# SCH_PCB_LAMOS_Moteur_2025-04-08.net
KiCad netlist of a schematic drawn in EasyEDA
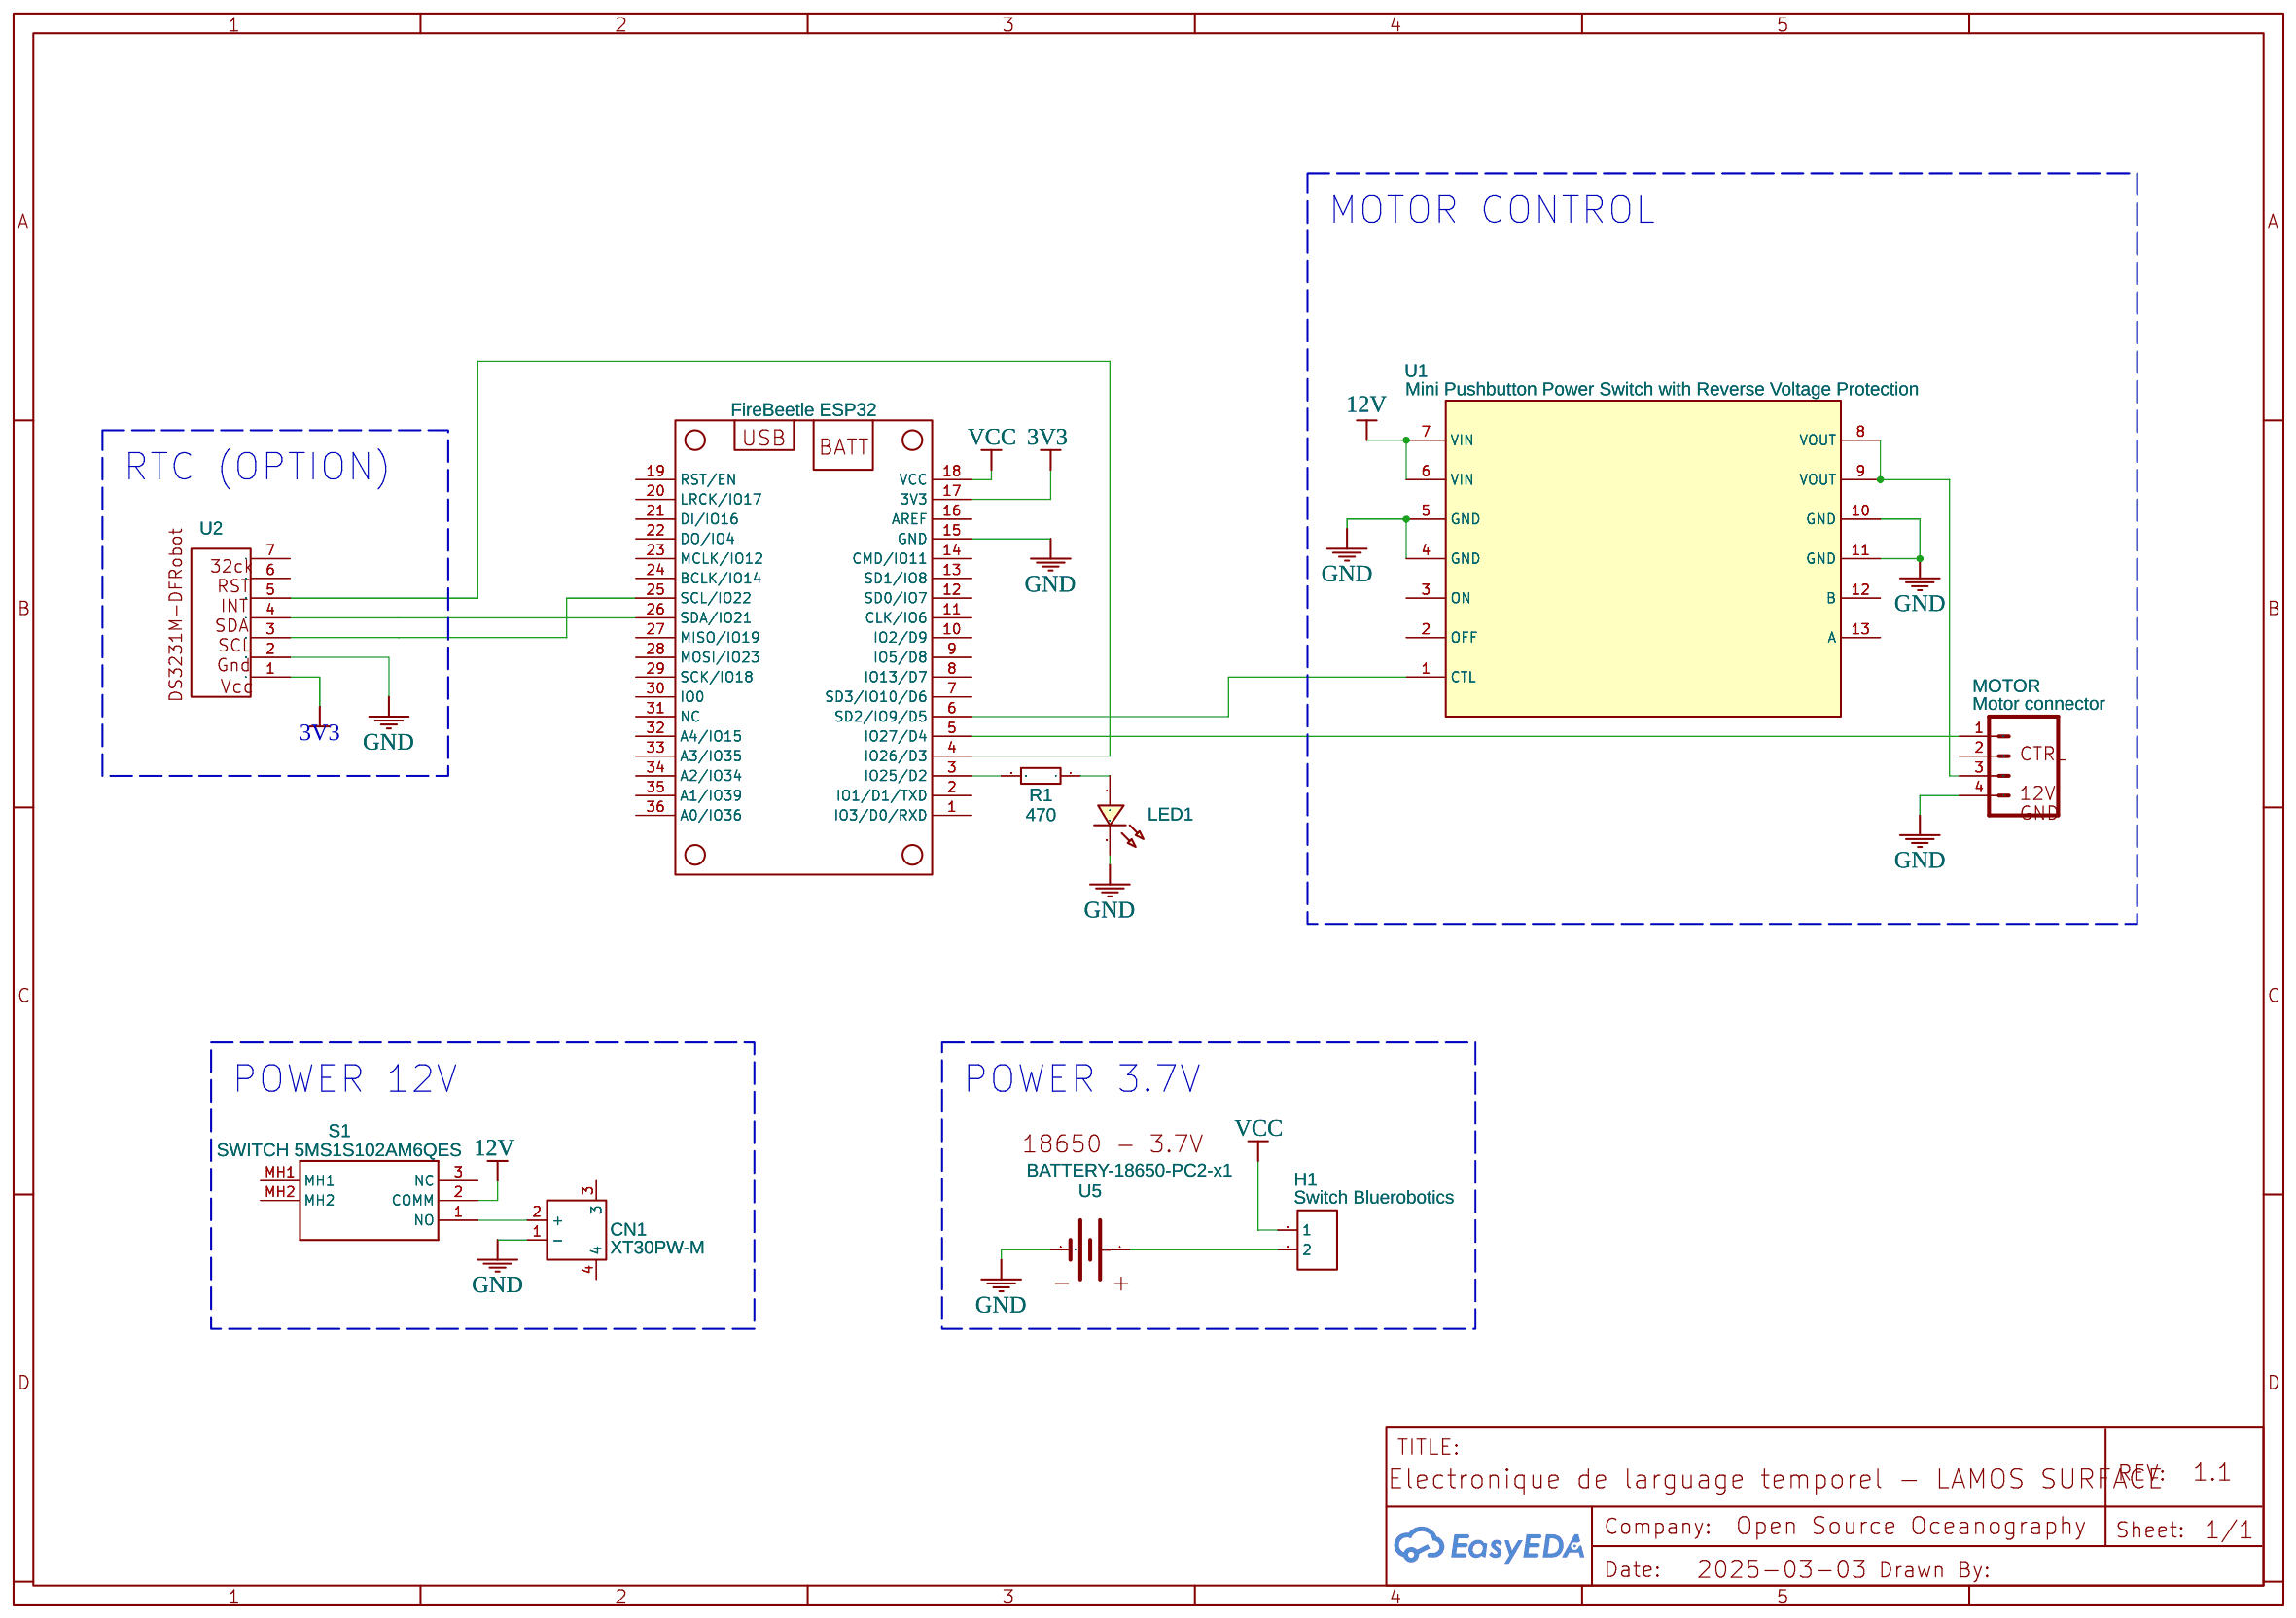
[diagram p0: schematic sheet]

(export (version "E")
  (design (tool "Eeschema 10.0.6"))
  (components
    (comp (ref "CN1")
      (value "XT30PW-M")
      (fields (field (name "Manufacturer Part") "XT30PW-M30.G.Y") (field (name "Manufacturer") "AMASS(艾迈斯)"))
      (libsource (lib "") (part "XT30PW-M"))
    )
    (comp (ref "ESP32-FB")
      (value "FireBeetle ESP32")
      (fields (field (name "Manufacturer Part") "?"))
      (libsource (lib "") (part "Unknown_405_-510"))
    )
    (comp (ref "H1") (value "Switch Bluerobotics") (libsource (lib "") (part "HDR-F-2.54_1x2")))
    (comp (ref "LED1")
      (value "LED-TH-3mm_G")
      (fields
        (field (name "Manufacturer Part") "204-10SYGD/S530-E3")
        (field (name "Manufacturer") "EVERLIGHT(台湾亿光)")
      )
      (libsource (lib "") (part "LED-TH-3mm_G"))
    )
    (comp (ref "MOTOR")
      (value "Motor connector")
      (fields (field (name "Manufacturer Part") "?"))
      (libsource (lib "") (part "Unknown_1010_-425"))
    )
    (comp (ref "R1")
      (value "470")
      (fields (field (name "Manufacturer Part") "?"))
      (libsource (lib "") (part "Res_AXIAL-0.3(1/8W)_EU"))
    )
    (comp (ref "S1") (value "SWITCH 5MS1S102AM6QES") (libsource (lib "") (part "5MS1S102AM6QES")))
    (comp (ref "U1")
      (value "Mini Pushbutton Power Switch with Reverse Voltage Protection")
      (libsource (lib "") (part "Mini Pushbutton Power Switch with Reverse Voltage Protection"))
    )
    (comp (ref "U2")
      (value "DS3231_DFRobot")
      (fields (field (name "Manufacturer Part") "DS3231M MEMS") (field (name "Manufacturer") "DFROBOT"))
      (libsource (lib "") (part "DS3231_DFRobot"))
    )
    (comp (ref "U5") (value "BATTERY-18650-PC2-x1") (libsource (lib "") (part "BATTERY-18650-PC2-x1")))
  )
  (nets
    (net (code "1") (name "3V3") (class "Default")
      (node (ref "ESP32-FB") (pin "17") (pinfunction "3V3_17") (pintype "unspecified"))
      (node (ref "U2") (pin "1") (pinfunction "1_1") (pintype "unspecified"))
    )
    (net (code "2") (name "12V") (class "Default")
      (node (ref "S1") (pin "2") (pinfunction "COMM_2") (pintype "bidirectional"))
      (node (ref "U1") (pin "6") (pinfunction "VIN_6") (pintype "unspecified"))
      (node (ref "U1") (pin "7") (pinfunction "VIN_7") (pintype "unspecified"))
    )
    (net (code "3") (name "GND") (class "Default")
      (node (ref "CN1") (pin "1") (pinfunction "-_1") (pintype "unspecified"))
      (node (ref "ESP32-FB") (pin "15") (pinfunction "GND_15") (pintype "unspecified"))
      (node (ref "LED1") (pin "2") (pinfunction "2_2") (pintype "unspecified"))
      (node (ref "MOTOR") (pin "4") (pinfunction "4_4") (pintype "unspecified"))
      (node (ref "U1") (pin "10") (pinfunction "GND_10") (pintype "unspecified"))
      (node (ref "U1") (pin "11") (pinfunction "GND_11") (pintype "unspecified"))
      (node (ref "U1") (pin "4") (pinfunction "GND_4") (pintype "unspecified"))
      (node (ref "U1") (pin "5") (pinfunction "GND_5") (pintype "unspecified"))
      (node (ref "U2") (pin "2") (pinfunction "2_2") (pintype "unspecified"))
      (node (ref "U5") (pin "2") (pinfunction "-_2") (pintype "passive"))
    )
    (net (code "4") (name "Net-(CN1-+)") (class "Default")
      (node (ref "CN1") (pin "2") (pinfunction "+_2") (pintype "unspecified"))
      (node (ref "S1") (pin "1") (pinfunction "NO_1") (pintype "bidirectional"))
    )
    (net (code "5") (name "Net-(ESP32-FB-IO25{slash}D2)") (class "Default")
      (node (ref "ESP32-FB") (pin "3") (pinfunction "IO25/D2_3") (pintype "unspecified"))
      (node (ref "R1") (pin "2") (pinfunction "2_2") (pintype "unspecified"))
    )
    (net (code "6") (name "Net-(ESP32-FB-IO26{slash}D3)") (class "Default")
      (node (ref "ESP32-FB") (pin "4") (pinfunction "IO26/D3_4") (pintype "unspecified"))
      (node (ref "U2") (pin "5") (pinfunction "5_5") (pintype "unspecified"))
    )
    (net (code "7") (name "Net-(ESP32-FB-IO27{slash}D4)") (class "Default")
      (node (ref "ESP32-FB") (pin "5") (pinfunction "IO27/D4_5") (pintype "unspecified"))
      (node (ref "MOTOR") (pin "1") (pinfunction "1_1") (pintype "unspecified"))
    )
    (net (code "8") (name "Net-(ESP32-FB-SCL{slash}IO22)") (class "Default")
      (node (ref "ESP32-FB") (pin "25") (pinfunction "SCL/IO22_25") (pintype "unspecified"))
      (node (ref "U2") (pin "3") (pinfunction "3_3") (pintype "unspecified"))
    )
    (net (code "9") (name "Net-(ESP32-FB-SD2{slash}IO9{slash}D5)") (class "Default")
      (node (ref "ESP32-FB") (pin "6") (pinfunction "SD2/IO9/D5_6") (pintype "unspecified"))
      (node (ref "U1") (pin "1") (pinfunction "CTL_1") (pintype "unspecified"))
    )
    (net (code "10") (name "Net-(ESP32-FB-SDA{slash}IO21)") (class "Default")
      (node (ref "ESP32-FB") (pin "26") (pinfunction "SDA/IO21_26") (pintype "unspecified"))
      (node (ref "U2") (pin "4") (pinfunction "4_4") (pintype "unspecified"))
    )
    (net (code "11") (name "Net-(LED1-Pad1)") (class "Default")
      (node (ref "LED1") (pin "1") (pinfunction "1_1") (pintype "unspecified"))
      (node (ref "R1") (pin "1") (pinfunction "1_1") (pintype "unspecified"))
    )
    (net (code "12") (name "Net-(MOTOR-Pad3)") (class "Default")
      (node (ref "MOTOR") (pin "3") (pinfunction "3_3") (pintype "unspecified"))
      (node (ref "U1") (pin "8") (pinfunction "VOUT_8") (pintype "unspecified"))
      (node (ref "U1") (pin "9") (pinfunction "VOUT_9") (pintype "unspecified"))
    )
    (net (code "13") (name "Net-(U5-+)") (class "Default")
      (node (ref "H1") (pin "2") (pinfunction "2_2") (pintype "input"))
      (node (ref "U5") (pin "1") (pinfunction "+_1") (pintype "passive"))
    )
    (net (code "14") (name "VCC") (class "Default")
      (node (ref "ESP32-FB") (pin "18") (pinfunction "VCC_18") (pintype "unspecified"))
      (node (ref "H1") (pin "1") (pinfunction "1_1") (pintype "input"))
    )
    (net (code "15") (name "unconnected-(CN1-Pad3)") (class "Default")
      (node (ref "CN1") (pin "3") (pinfunction "3_3") (pintype "unspecified"))
    )
    (net (code "16") (name "unconnected-(CN1-Pad4)") (class "Default")
      (node (ref "CN1") (pin "4") (pinfunction "4_4") (pintype "unspecified"))
    )
    (net (code "17") (name "unconnected-(ESP32-FB-A0{slash}IO36-Pad36)") (class "Default")
      (node (ref "ESP32-FB") (pin "36") (pinfunction "A0/IO36_36") (pintype "unspecified"))
    )
    (net (code "18") (name "unconnected-(ESP32-FB-A1{slash}IO39-Pad35)") (class "Default")
      (node (ref "ESP32-FB") (pin "35") (pinfunction "A1/IO39_35") (pintype "unspecified"))
    )
    (net (code "19") (name "unconnected-(ESP32-FB-A2{slash}IO34-Pad34)") (class "Default")
      (node (ref "ESP32-FB") (pin "34") (pinfunction "A2/IO34_34") (pintype "unspecified"))
    )
    (net (code "20") (name "unconnected-(ESP32-FB-A3{slash}IO35-Pad33)") (class "Default")
      (node (ref "ESP32-FB") (pin "33") (pinfunction "A3/IO35_33") (pintype "unspecified"))
    )
    (net (code "21") (name "unconnected-(ESP32-FB-A4{slash}IO15-Pad32)") (class "Default")
      (node (ref "ESP32-FB") (pin "32") (pinfunction "A4/IO15_32") (pintype "unspecified"))
    )
    (net (code "22") (name "unconnected-(ESP32-FB-AREF-Pad16)") (class "Default")
      (node (ref "ESP32-FB") (pin "16") (pinfunction "AREF_16") (pintype "unspecified"))
    )
    (net (code "23") (name "unconnected-(ESP32-FB-BCLK{slash}IO14-Pad24)") (class "Default")
      (node (ref "ESP32-FB") (pin "24") (pinfunction "BCLK/IO14_24") (pintype "unspecified"))
    )
    (net (code "24") (name "unconnected-(ESP32-FB-CLK{slash}IO6-Pad11)") (class "Default")
      (node (ref "ESP32-FB") (pin "11") (pinfunction "CLK/IO6_11") (pintype "unspecified"))
    )
    (net (code "25") (name "unconnected-(ESP32-FB-CMD{slash}IO11-Pad14)") (class "Default")
      (node (ref "ESP32-FB") (pin "14") (pinfunction "CMD/IO11_14") (pintype "unspecified"))
    )
    (net (code "26") (name "unconnected-(ESP32-FB-DI{slash}IO16-Pad21)") (class "Default")
      (node (ref "ESP32-FB") (pin "21") (pinfunction "DI/IO16_21") (pintype "unspecified"))
    )
    (net (code "27") (name "unconnected-(ESP32-FB-DO{slash}IO4-Pad22)") (class "Default")
      (node (ref "ESP32-FB") (pin "22") (pinfunction "DO/IO4_22") (pintype "unspecified"))
    )
    (net (code "28") (name "unconnected-(ESP32-FB-IO0-Pad30)") (class "Default")
      (node (ref "ESP32-FB") (pin "30") (pinfunction "IO0_30") (pintype "unspecified"))
    )
    (net (code "29") (name "unconnected-(ESP32-FB-IO1{slash}D1{slash}TXD-Pad2)") (class "Default")
      (node (ref "ESP32-FB") (pin "2") (pinfunction "IO1/D1/TXD_2") (pintype "unspecified"))
    )
    (net (code "30") (name "unconnected-(ESP32-FB-IO2{slash}D9-Pad10)") (class "Default")
      (node (ref "ESP32-FB") (pin "10") (pinfunction "IO2/D9_10") (pintype "unspecified"))
    )
    (net (code "31") (name "unconnected-(ESP32-FB-IO3{slash}D0{slash}RXD-Pad1)") (class "Default")
      (node (ref "ESP32-FB") (pin "1") (pinfunction "IO3/D0/RXD_1") (pintype "unspecified"))
    )
    (net (code "32") (name "unconnected-(ESP32-FB-IO5{slash}D8-Pad9)") (class "Default")
      (node (ref "ESP32-FB") (pin "9") (pinfunction "IO5/D8_9") (pintype "unspecified"))
    )
    (net (code "33") (name "unconnected-(ESP32-FB-IO13{slash}D7-Pad8)") (class "Default")
      (node (ref "ESP32-FB") (pin "8") (pinfunction "IO13/D7_8") (pintype "unspecified"))
    )
    (net (code "34") (name "unconnected-(ESP32-FB-LRCK{slash}IO17-Pad20)") (class "Default")
      (node (ref "ESP32-FB") (pin "20") (pinfunction "LRCK/IO17_20") (pintype "unspecified"))
    )
    (net (code "35") (name "unconnected-(ESP32-FB-MCLK{slash}IO12-Pad23)") (class "Default")
      (node (ref "ESP32-FB") (pin "23") (pinfunction "MCLK/IO12_23") (pintype "unspecified"))
    )
    (net (code "36") (name "unconnected-(ESP32-FB-MISO{slash}IO19-Pad27)") (class "Default")
      (node (ref "ESP32-FB") (pin "27") (pinfunction "MISO/IO19_27") (pintype "unspecified"))
    )
    (net (code "37") (name "unconnected-(ESP32-FB-MOSI{slash}IO23-Pad28)") (class "Default")
      (node (ref "ESP32-FB") (pin "28") (pinfunction "MOSI/IO23_28") (pintype "unspecified"))
    )
    (net (code "38") (name "unconnected-(ESP32-FB-NC-Pad31)") (class "Default")
      (node (ref "ESP32-FB") (pin "31") (pinfunction "NC_31") (pintype "unspecified"))
    )
    (net (code "39") (name "unconnected-(ESP32-FB-RST{slash}EN-Pad19)") (class "Default")
      (node (ref "ESP32-FB") (pin "19") (pinfunction "RST/EN_19") (pintype "input"))
    )
    (net (code "40") (name "unconnected-(ESP32-FB-SCK{slash}IO18-Pad29)") (class "Default")
      (node (ref "ESP32-FB") (pin "29") (pinfunction "SCK/IO18_29") (pintype "unspecified"))
    )
    (net (code "41") (name "unconnected-(ESP32-FB-SD0{slash}IO7-Pad12)") (class "Default")
      (node (ref "ESP32-FB") (pin "12") (pinfunction "SD0/IO7_12") (pintype "unspecified"))
    )
    (net (code "42") (name "unconnected-(ESP32-FB-SD1{slash}IO8-Pad13)") (class "Default")
      (node (ref "ESP32-FB") (pin "13") (pinfunction "SD1/IO8_13") (pintype "unspecified"))
    )
    (net (code "43") (name "unconnected-(ESP32-FB-SD3{slash}IO10{slash}D6-Pad7)") (class "Default")
      (node (ref "ESP32-FB") (pin "7") (pinfunction "SD3/IO10/D6_7") (pintype "unspecified"))
    )
    (net (code "44") (name "unconnected-(MOTOR-Pad2)") (class "Default")
      (node (ref "MOTOR") (pin "2") (pinfunction "2_2") (pintype "unspecified"))
    )
    (net (code "45") (name "unconnected-(S1-NC-Pad3)") (class "Default")
      (node (ref "S1") (pin "3") (pinfunction "NC_3") (pintype "bidirectional"))
    )
    (net (code "46") (name "unconnected-(S1-PadMH1)") (class "Default")
      (node (ref "S1") (pin "MH1") (pinfunction "MH1_MH1") (pintype "bidirectional"))
    )
    (net (code "47") (name "unconnected-(S1-PadMH2)") (class "Default")
      (node (ref "S1") (pin "MH2") (pinfunction "MH2_MH2") (pintype "bidirectional"))
    )
    (net (code "48") (name "unconnected-(U1-A-Pad13)") (class "Default")
      (node (ref "U1") (pin "13") (pinfunction "A_13") (pintype "unspecified"))
    )
    (net (code "49") (name "unconnected-(U1-B-Pad12)") (class "Default")
      (node (ref "U1") (pin "12") (pinfunction "B_12") (pintype "unspecified"))
    )
    (net (code "50") (name "unconnected-(U1-OFF-Pad2)") (class "Default")
      (node (ref "U1") (pin "2") (pinfunction "OFF_2") (pintype "unspecified"))
    )
    (net (code "51") (name "unconnected-(U1-ON-Pad3)") (class "Default")
      (node (ref "U1") (pin "3") (pinfunction "ON_3") (pintype "unspecified"))
    )
    (net (code "52") (name "unconnected-(U2-Pad6)") (class "Default")
      (node (ref "U2") (pin "6") (pinfunction "6_6") (pintype "unspecified"))
    )
    (net (code "53") (name "unconnected-(U2-Pad7)") (class "Default")
      (node (ref "U2") (pin "7") (pinfunction "7_7") (pintype "unspecified"))
    )
  )
)
